# aansluiting.net
KiCad netlist of a schematic drawn in Altium Designer
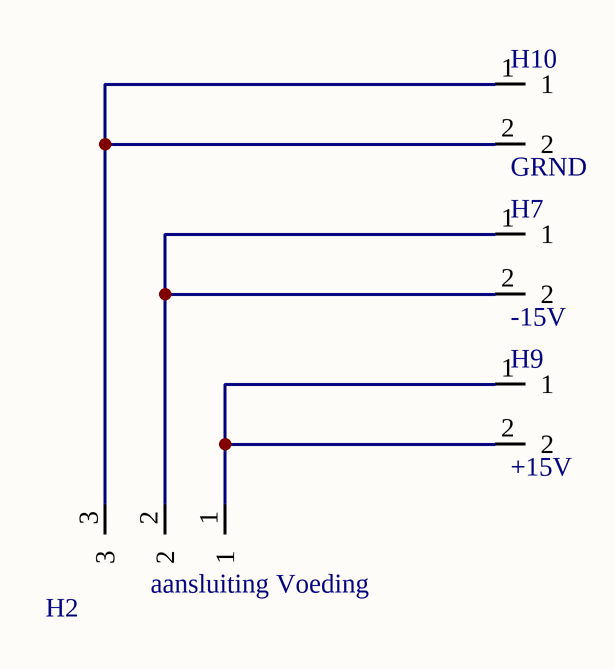
[diagram p0: aansluiting.SchDoc]

(export (version "E")
  (design (tool "Eeschema 10.0.6"))
  (components
    (comp (ref "H2")
      (value "aansluiting Voeding")
      (footprint "header 1x3")
      (libsource (lib "headerSchematicLibrary") (part "header 1x3"))
    )
    (comp (ref "H7")
      (value "-15V")
      (footprint "header 1x2")
      (libsource (lib "headerSchematicLibrary") (part "header 1x2"))
    )
    (comp (ref "H9")
      (value "+15V")
      (footprint "header 1x2")
      (libsource (lib "headerSchematicLibrary") (part "header 1x2"))
    )
    (comp (ref "H10")
      (value "GRND")
      (footprint "header 1x2")
      (libsource (lib "headerSchematicLibrary") (part "header 1x2"))
    )
  )
  (nets
    (net (code "1") (name "Net-(H2-Pad1)") (class "Default")
      (node (ref "H2") (pin "1") (pinfunction "1_1") (pintype "passive"))
      (node (ref "H9") (pin "1") (pinfunction "1_1") (pintype "passive"))
      (node (ref "H9") (pin "2") (pinfunction "2_2") (pintype "passive"))
    )
    (net (code "2") (name "Net-(H2-Pad2)") (class "Default")
      (node (ref "H2") (pin "2") (pinfunction "2_2") (pintype "passive"))
      (node (ref "H7") (pin "1") (pinfunction "1_1") (pintype "passive"))
      (node (ref "H7") (pin "2") (pinfunction "2_2") (pintype "passive"))
    )
    (net (code "3") (name "Net-(H10-Pad1)") (class "Default")
      (node (ref "H10") (pin "1") (pinfunction "1_1") (pintype "passive"))
      (node (ref "H10") (pin "2") (pinfunction "2_2") (pintype "passive"))
      (node (ref "H2") (pin "3") (pinfunction "3_3") (pintype "passive"))
    )
  )
)
